# H3AR0.net
KiCad netlist of a schematic drawn in EAGLE
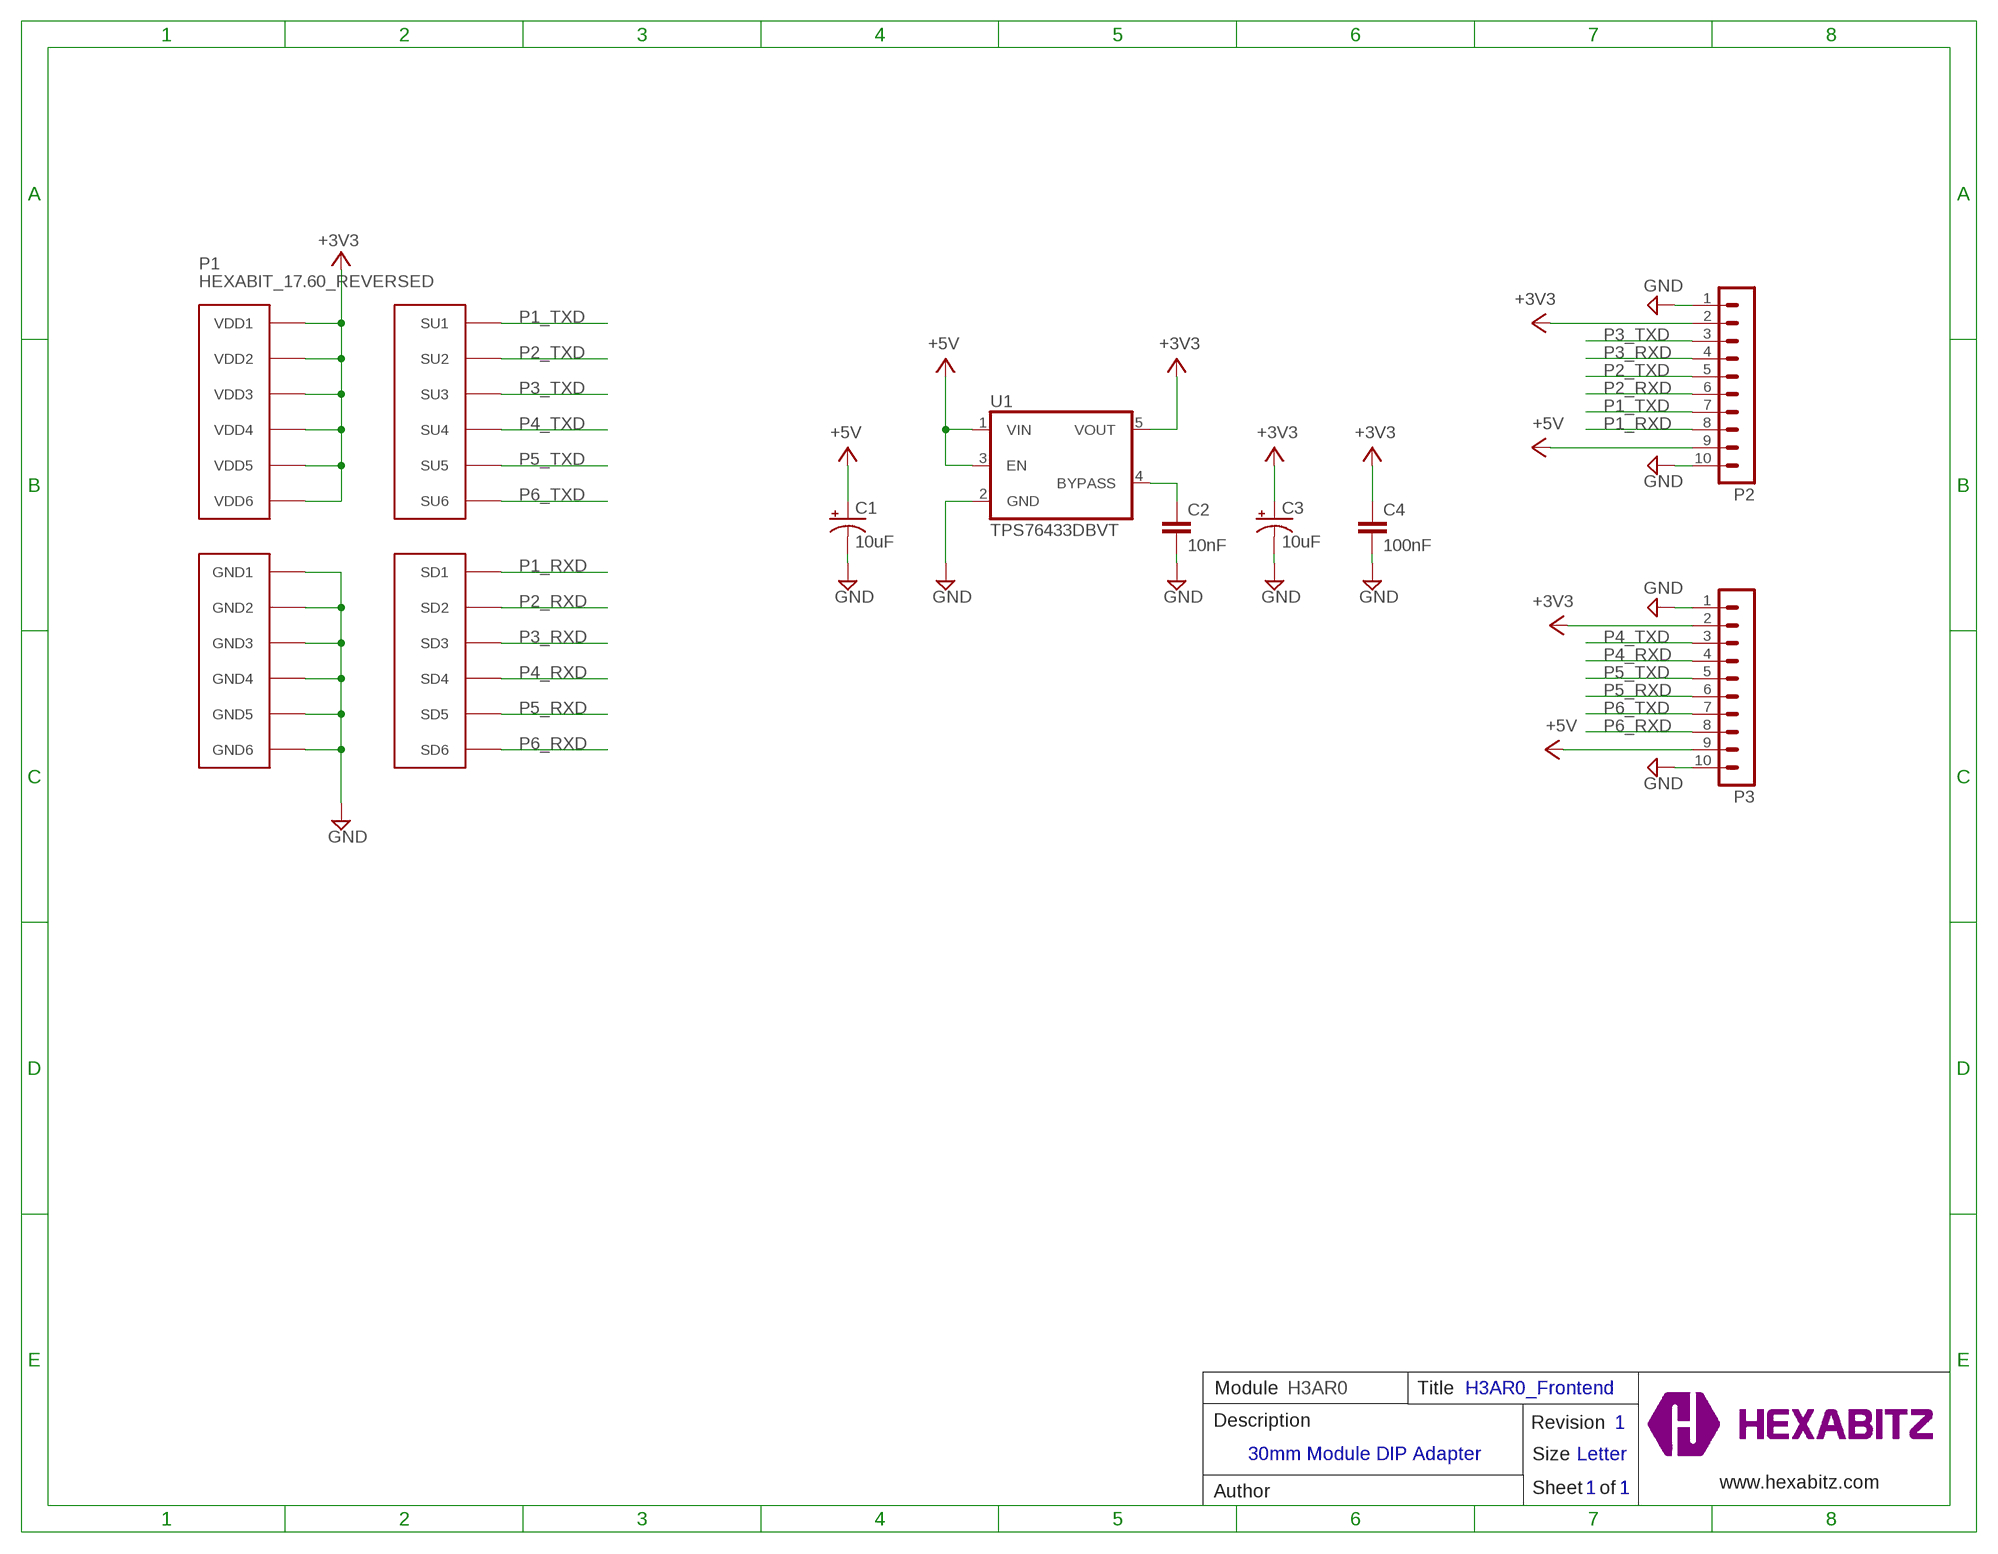
[diagram p0: schematic, sheet 1]

(export (version "E")
  (design (tool "Eeschema 10.0.6"))
  (components
    (comp (ref "C1")
      (value "10uF")
      (footprint "eagle-import:C-1210-POL")
      (fields
        (field (name "CAPACITANCE") "10uF")
        (field (name "MFN") "AVX")
        (field (name "MPN") "TPSB106K016R0500")
        (field (name "OCTOPART_URL") "https://octopart.com/tpsb106k016r0500-avx-1436890?r=sp#")
      )
      (libsource (lib "eagle-import") (part "C-1210-POL"))
    )
    (comp (ref "C2")
      (value "10nF")
      (footprint "eagle-import:C-0603")
      (fields
        (field (name "CAPACITANCE") "10nF")
        (field (name "MFN") "KEMET")
        (field (name "MPN") "C0603C103K5RACTU")
        (field (name "OCTOPART_URL") "https://octopart.com/c0603c103k5ractu-kemet-133094?r=sp&s=R_iPBxLnSmGqhkU2rIMFpg")
        (field (name "TOLERANCE") "10%")
        (field (name "VOLTAGE_RATING") "50V")
      )
      (libsource (lib "eagle-import") (part "C-0603"))
    )
    (comp (ref "C3")
      (value "10uF")
      (footprint "eagle-import:C-1210-POL")
      (fields
        (field (name "CAPACITANCE") "10uF")
        (field (name "MFN") "AVX")
        (field (name "MPN") "TPSB106K016R0500")
        (field (name "OCTOPART_URL") "https://octopart.com/tpsb106k016r0500-avx-1436890?r=sp#")
      )
      (libsource (lib "eagle-import") (part "C-1210-POL"))
    )
    (comp (ref "C4")
      (value "100nF")
      (footprint "eagle-import:C-0603")
      (fields
        (field (name "CAPACITANCE") "100nF")
        (field (name "MFN") "KEMET")
        (field (name "MPN") "C0603C104K8RACTU")
        (field (name "OCTOPART_URL") "https://octopart.com/c0603c104k8ractu-kemet-145075?r=sp&s=9bS9ASSwSEqMCE9KBEQZ0g")
        (field (name "TOLERANCE") "10%")
        (field (name "VOLTAGE_RATING") "10V")
      )
      (libsource (lib "eagle-import") (part "C-0603"))
    )
    (comp (ref "P1")
      (value "HEXABIT_17.60_REVERSED")
      (footprint "eagle-import:HEXABIT_17.60_REVERSED")
      (libsource (lib "eagle-import") (part "HEXABIT_?_REVERSED17.60"))
    )
    (comp (ref "P2")
      (value "MA10-1")
      (footprint "eagle-import:MA10-1")
      (fields (field (name "MPN") "61301011121"))
      (libsource (lib "eagle-import") (part "MA10-1"))
    )
    (comp (ref "P3")
      (value "MA10-1")
      (footprint "eagle-import:MA10-1")
      (fields (field (name "MPN") "61301011121"))
      (libsource (lib "eagle-import") (part "MA10-1"))
    )
    (comp (ref "TRIMBLE-LOGO1")
      (value "HEXA-LOGO")
      (footprint "eagle-import:HEXA-LOGO")
      (libsource (lib "eagle-import") (part "HEXA-LOGO"))
    )
    (comp (ref "U1")
      (value "TPS76433DBVT")
      (footprint "eagle-import:SOT25")
      (libsource (lib "eagle-import") (part "TPS764DBVT33"))
    )
  )
  (nets
    (net (code "1") (name "+3V3") (class "Default")
      (node (ref "C3") (pin "1") (pinfunction "+_1") (pintype "passive"))
      (node (ref "C4") (pin "1") (pinfunction "1_1") (pintype "passive"))
      (node (ref "P1") (pin "PAD_PU10") (pinfunction "VDD4_PAD_PU10") (pintype "power_in"))
      (node (ref "P1") (pin "PAD_PU11") (pinfunction "VDD5_PAD_PU11") (pintype "power_in"))
      (node (ref "P1") (pin "PAD_PU12") (pinfunction "VDD6_PAD_PU12") (pintype "power_in"))
      (node (ref "P1") (pin "PAD_PU7") (pinfunction "VDD1_PAD_PU7") (pintype "power_in"))
      (node (ref "P1") (pin "PAD_PU8") (pinfunction "VDD2_PAD_PU8") (pintype "power_in"))
      (node (ref "P1") (pin "PAD_PU9") (pinfunction "VDD3_PAD_PU9") (pintype "power_in"))
      (node (ref "P2") (pin "2") (pinfunction "2_2") (pintype "passive"))
      (node (ref "P3") (pin "2") (pinfunction "2_2") (pintype "passive"))
      (node (ref "U1") (pin "5") (pinfunction "VOUT_5") (pintype "passive"))
    )
    (net (code "2") (name "+5V") (class "Default")
      (node (ref "C1") (pin "1") (pinfunction "+_1") (pintype "passive"))
      (node (ref "P2") (pin "9") (pinfunction "9_9") (pintype "passive"))
      (node (ref "P3") (pin "9") (pinfunction "9_9") (pintype "passive"))
      (node (ref "U1") (pin "1") (pinfunction "VIN_1") (pintype "input"))
      (node (ref "U1") (pin "3") (pinfunction "EN_3") (pintype "input"))
    )
    (net (code "3") (name "/P1_RXD") (class "Default")
      (node (ref "P1") (pin "PAD_PD1") (pinfunction "SD1_PAD_PD1") (pintype "bidirectional"))
      (node (ref "P2") (pin "8") (pinfunction "8_8") (pintype "passive"))
    )
    (net (code "4") (name "/P1_TXD") (class "Default")
      (node (ref "P1") (pin "PAD_PU1") (pinfunction "SU1_PAD_PU1") (pintype "bidirectional"))
      (node (ref "P2") (pin "7") (pinfunction "7_7") (pintype "passive"))
    )
    (net (code "5") (name "/P2_RXD") (class "Default")
      (node (ref "P1") (pin "PAD_PD2") (pinfunction "SD2_PAD_PD2") (pintype "bidirectional"))
      (node (ref "P2") (pin "6") (pinfunction "6_6") (pintype "passive"))
    )
    (net (code "6") (name "/P2_TXD") (class "Default")
      (node (ref "P1") (pin "PAD_PU2") (pinfunction "SU2_PAD_PU2") (pintype "bidirectional"))
      (node (ref "P2") (pin "5") (pinfunction "5_5") (pintype "passive"))
    )
    (net (code "7") (name "/P3_RXD") (class "Default")
      (node (ref "P1") (pin "PAD_PD3") (pinfunction "SD3_PAD_PD3") (pintype "bidirectional"))
      (node (ref "P2") (pin "4") (pinfunction "4_4") (pintype "passive"))
    )
    (net (code "8") (name "/P3_TXD") (class "Default")
      (node (ref "P1") (pin "PAD_PU3") (pinfunction "SU3_PAD_PU3") (pintype "bidirectional"))
      (node (ref "P2") (pin "3") (pinfunction "3_3") (pintype "passive"))
    )
    (net (code "9") (name "/P4_RXD") (class "Default")
      (node (ref "P1") (pin "PAD_PD4") (pinfunction "SD4_PAD_PD4") (pintype "bidirectional"))
      (node (ref "P3") (pin "4") (pinfunction "4_4") (pintype "passive"))
    )
    (net (code "10") (name "/P4_TXD") (class "Default")
      (node (ref "P1") (pin "PAD_PU4") (pinfunction "SU4_PAD_PU4") (pintype "bidirectional"))
      (node (ref "P3") (pin "3") (pinfunction "3_3") (pintype "passive"))
    )
    (net (code "11") (name "/P5_RXD") (class "Default")
      (node (ref "P1") (pin "PAD_PD5") (pinfunction "SD5_PAD_PD5") (pintype "bidirectional"))
      (node (ref "P3") (pin "6") (pinfunction "6_6") (pintype "passive"))
    )
    (net (code "12") (name "/P5_TXD") (class "Default")
      (node (ref "P1") (pin "PAD_PU5") (pinfunction "SU5_PAD_PU5") (pintype "bidirectional"))
      (node (ref "P3") (pin "5") (pinfunction "5_5") (pintype "passive"))
    )
    (net (code "13") (name "/P6_RXD") (class "Default")
      (node (ref "P1") (pin "PAD_PD6") (pinfunction "SD6_PAD_PD6") (pintype "bidirectional"))
      (node (ref "P3") (pin "8") (pinfunction "8_8") (pintype "passive"))
    )
    (net (code "14") (name "/P6_TXD") (class "Default")
      (node (ref "P1") (pin "PAD_PU6") (pinfunction "SU6_PAD_PU6") (pintype "bidirectional"))
      (node (ref "P3") (pin "7") (pinfunction "7_7") (pintype "passive"))
    )
    (net (code "15") (name "GND") (class "Default")
      (node (ref "C1") (pin "2") (pinfunction "-_2") (pintype "passive"))
      (node (ref "C2") (pin "2") (pinfunction "2_2") (pintype "passive"))
      (node (ref "C3") (pin "2") (pinfunction "-_2") (pintype "passive"))
      (node (ref "C4") (pin "2") (pinfunction "2_2") (pintype "passive"))
      (node (ref "P1") (pin "PAD_PD10") (pinfunction "GND4_PAD_PD10") (pintype "power_in"))
      (node (ref "P1") (pin "PAD_PD11") (pinfunction "GND5_PAD_PD11") (pintype "power_in"))
      (node (ref "P1") (pin "PAD_PD12") (pinfunction "GND6_PAD_PD12") (pintype "power_in"))
      (node (ref "P1") (pin "PAD_PD7") (pinfunction "GND1_PAD_PD7") (pintype "power_in"))
      (node (ref "P1") (pin "PAD_PD8") (pinfunction "GND2_PAD_PD8") (pintype "power_in"))
      (node (ref "P1") (pin "PAD_PD9") (pinfunction "GND3_PAD_PD9") (pintype "power_in"))
      (node (ref "P2") (pin "1") (pinfunction "1_1") (pintype "passive"))
      (node (ref "P2") (pin "10") (pinfunction "10_10") (pintype "passive"))
      (node (ref "P3") (pin "1") (pinfunction "1_1") (pintype "passive"))
      (node (ref "P3") (pin "10") (pinfunction "10_10") (pintype "passive"))
      (node (ref "U1") (pin "2") (pinfunction "GND_2") (pintype "passive"))
    )
    (net (code "16") (name "Net-(U1-BYPASS)") (class "Default")
      (node (ref "C2") (pin "1") (pinfunction "1_1") (pintype "passive"))
      (node (ref "U1") (pin "4") (pinfunction "BYPASS_4") (pintype "input"))
    )
  )
)
